# main_circuit.net
KiCad netlist of a schematic drawn in EAGLE
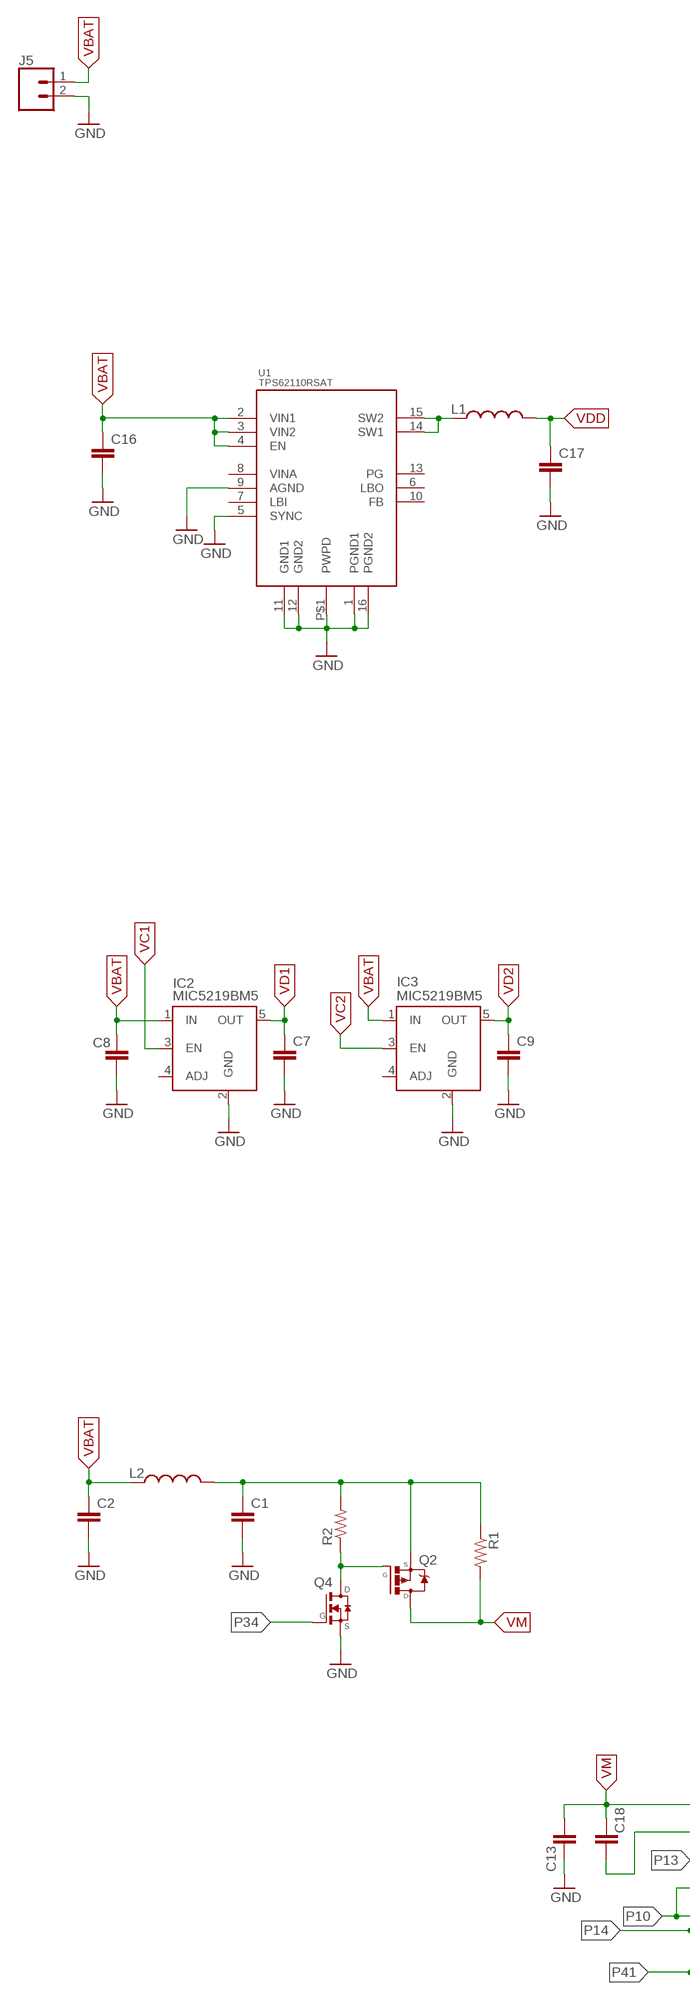
[diagram p0: schematic, sheet 1, part 1 of 2]
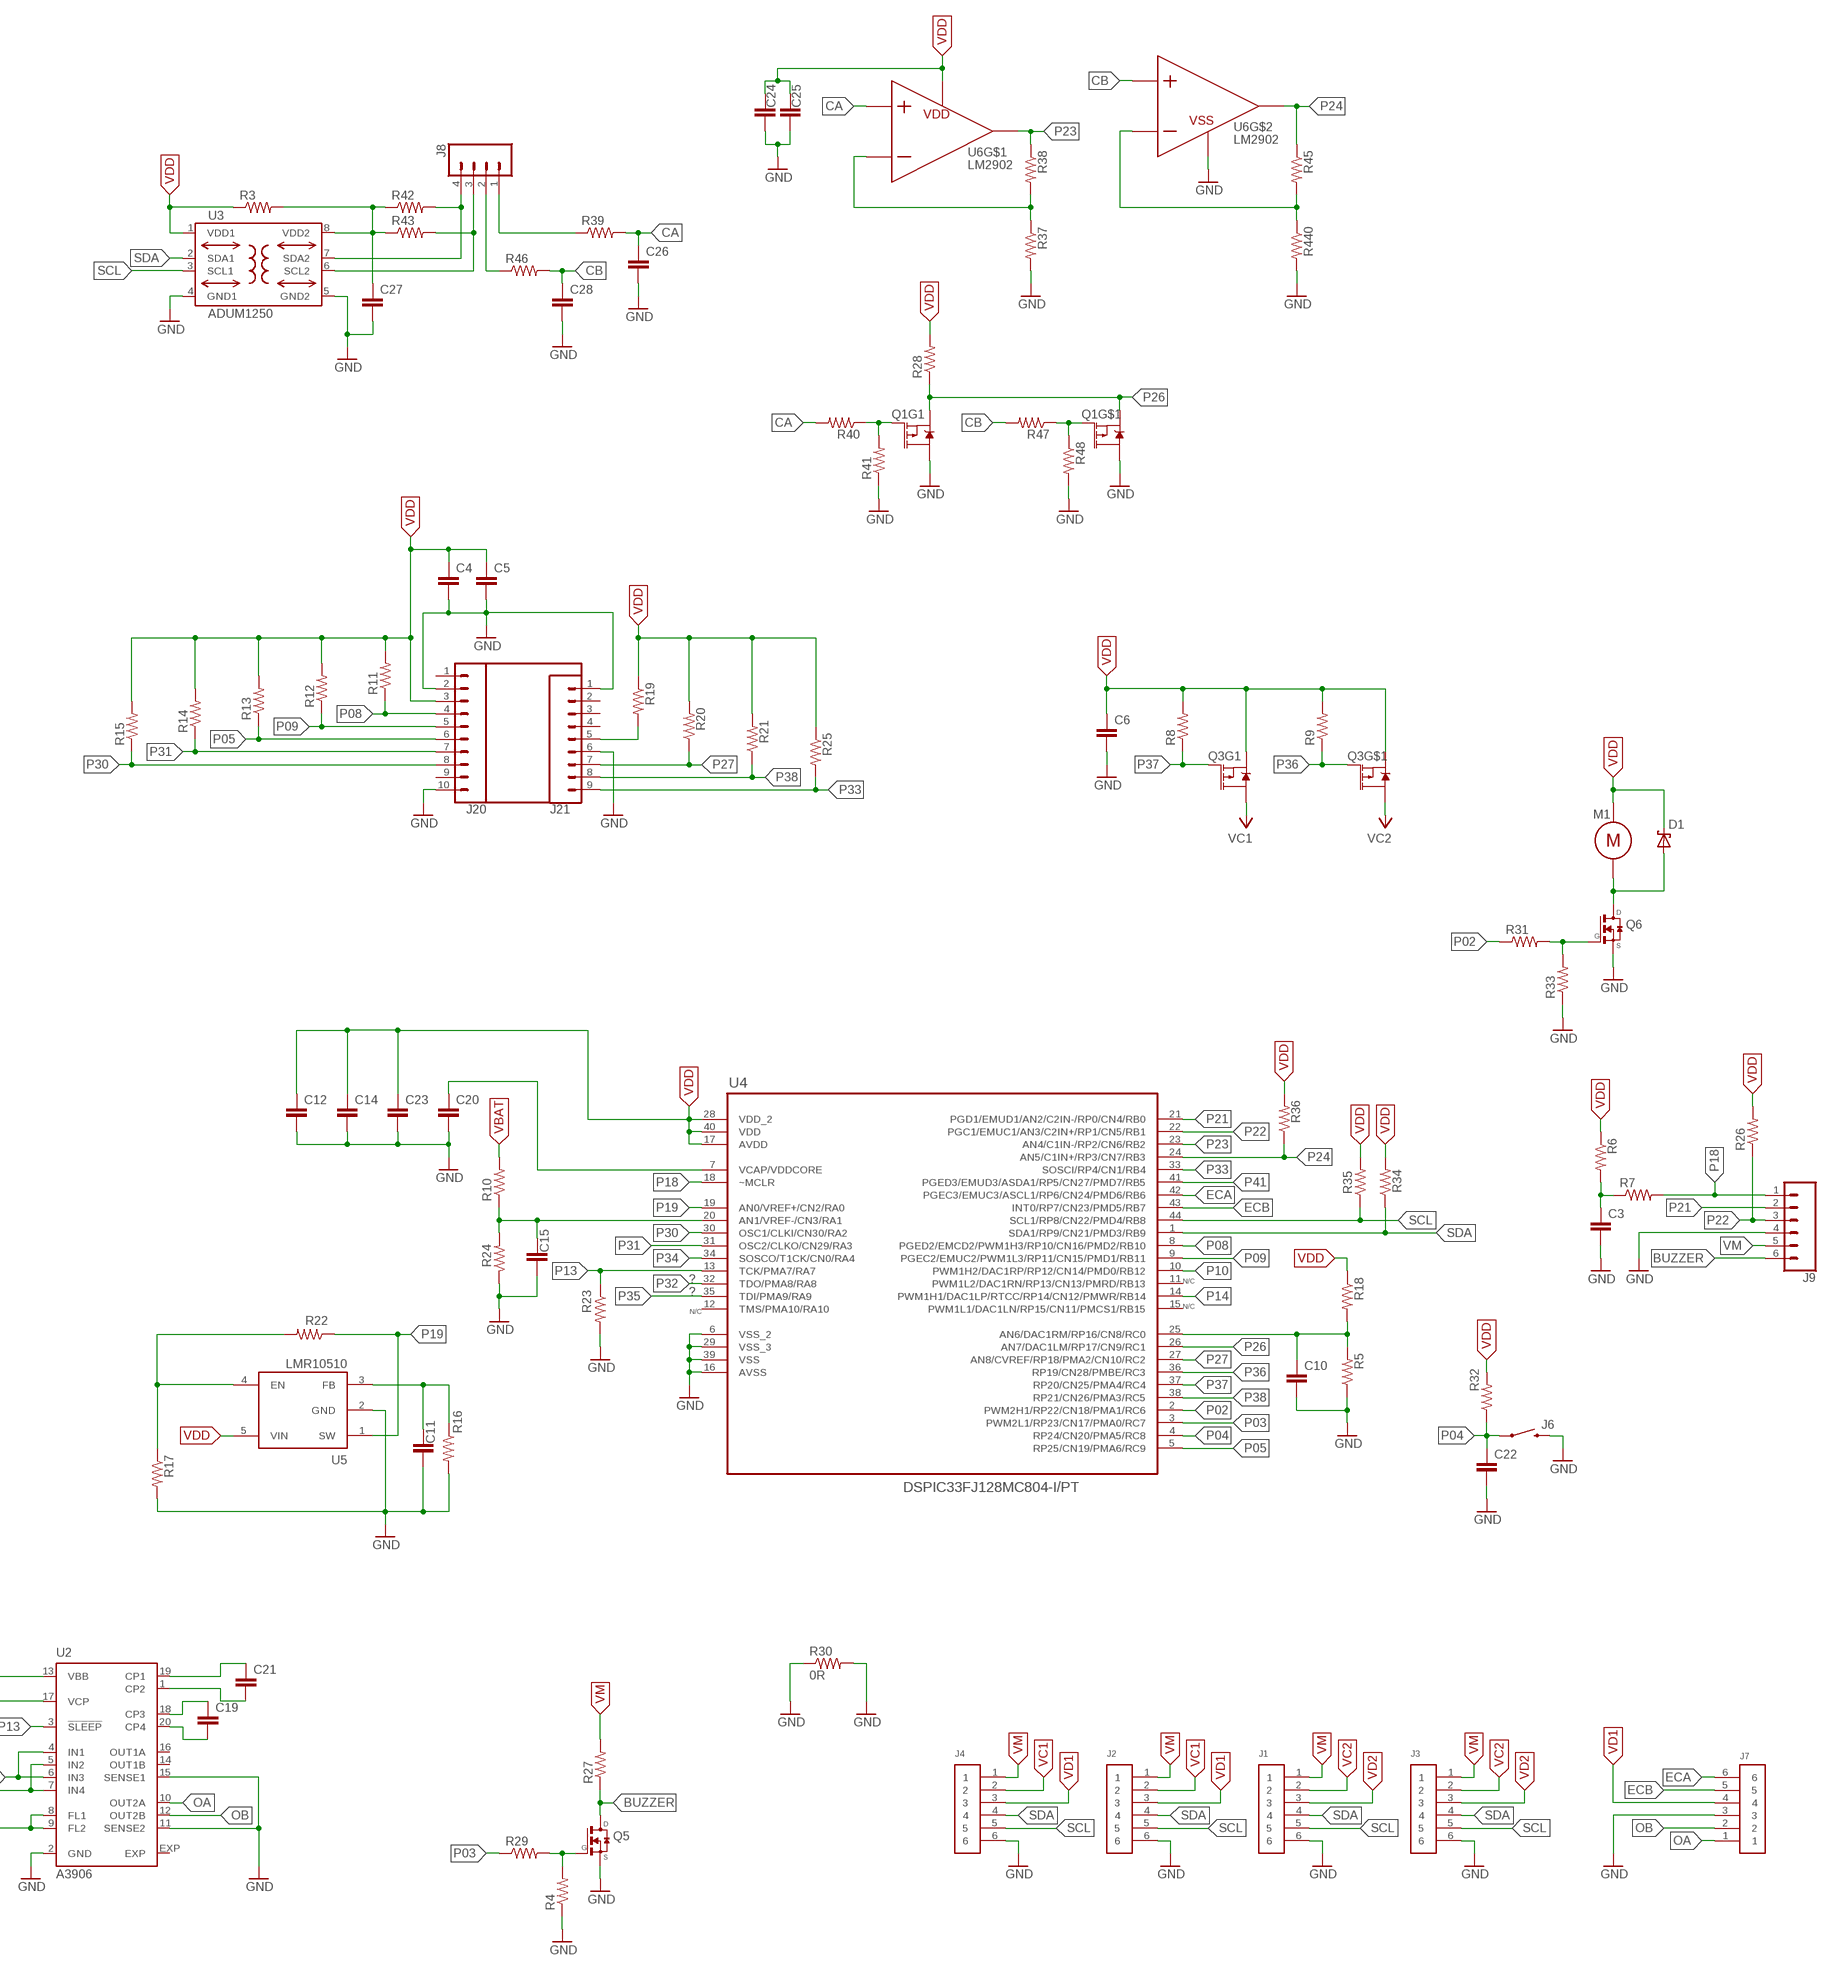
[diagram p1: schematic, sheet 1, part 2 of 2]

(export (version "E")
  (design (tool "Eeschema 10.0.6"))
  (components
    (comp (ref "C1")
      (value "C-EUC0805")
      (footprint "eagle-import:C0805")
      (libsource (lib "eagle-import") (part "C-EUC0805"))
    )
    (comp (ref "C2")
      (value "C-EUC0805")
      (footprint "eagle-import:C0805")
      (libsource (lib "eagle-import") (part "C-EUC0805"))
    )
    (comp (ref "C3")
      (value "CAPACITOR_0805_M")
      (footprint "eagle-import:RESC0805_M")
      (libsource (lib "eagle-import") (part "CAPACITOR_0805_M"))
    )
    (comp (ref "C4")
      (value "CAPACITOR_0805_M")
      (footprint "eagle-import:RESC0805_M")
      (libsource (lib "eagle-import") (part "CAPACITOR_0805_M"))
    )
    (comp (ref "C5")
      (value "CAPACITOR_0805_M")
      (footprint "eagle-import:RESC0805_M")
      (libsource (lib "eagle-import") (part "CAPACITOR_0805_M"))
    )
    (comp (ref "C6")
      (value "C-EUC0805")
      (footprint "eagle-import:C0805")
      (libsource (lib "eagle-import") (part "C-EUC0805"))
    )
    (comp (ref "C7")
      (value "CAPACITOR_0805_M")
      (footprint "eagle-import:RESC0805_M")
      (libsource (lib "eagle-import") (part "CAPACITOR_0805_M"))
    )
    (comp (ref "C8")
      (value "CAPACITOR_0805_M")
      (footprint "eagle-import:RESC0805_M")
      (libsource (lib "eagle-import") (part "CAPACITOR_0805_M"))
    )
    (comp (ref "C9")
      (value "CAPACITOR_0805_M")
      (footprint "eagle-import:RESC0805_M")
      (libsource (lib "eagle-import") (part "CAPACITOR_0805_M"))
    )
    (comp (ref "C10")
      (value "CAPACITOR_0805_M")
      (footprint "eagle-import:RESC0805_M")
      (libsource (lib "eagle-import") (part "CAPACITOR_0805_M"))
    )
    (comp (ref "C11")
      (value "CAPACITOR_0805_M")
      (footprint "eagle-import:RESC0805_M")
      (libsource (lib "eagle-import") (part "CAPACITOR_0805_M"))
    )
    (comp (ref "C12")
      (value "CAPACITOR_0805_M")
      (footprint "eagle-import:RESC0805_M")
      (libsource (lib "eagle-import") (part "CAPACITOR_0805_M"))
    )
    (comp (ref "C13")
      (value "CAPACITOR_0805_M")
      (footprint "eagle-import:RESC0805_M")
      (libsource (lib "eagle-import") (part "CAPACITOR_0805_M"))
    )
    (comp (ref "C14")
      (value "CAPACITOR_0805_M")
      (footprint "eagle-import:RESC0805_M")
      (libsource (lib "eagle-import") (part "CAPACITOR_0805_M"))
    )
    (comp (ref "C15")
      (value "CAPACITOR_0805_M")
      (footprint "eagle-import:RESC0805_M")
      (libsource (lib "eagle-import") (part "CAPACITOR_0805_M"))
    )
    (comp (ref "C16")
      (value "CAPACITOR_0805_M")
      (footprint "eagle-import:RESC0805_M")
      (libsource (lib "eagle-import") (part "CAPACITOR_0805_M"))
    )
    (comp (ref "C17")
      (value "CAPACITOR_0805_M")
      (footprint "eagle-import:RESC0805_M")
      (libsource (lib "eagle-import") (part "CAPACITOR_0805_M"))
    )
    (comp (ref "C18")
      (value "CAPACITOR_0805_M")
      (footprint "eagle-import:RESC0805_M")
      (libsource (lib "eagle-import") (part "CAPACITOR_0805_M"))
    )
    (comp (ref "C19")
      (value "CAPACITOR_0805_M")
      (footprint "eagle-import:RESC0805_M")
      (libsource (lib "eagle-import") (part "CAPACITOR_0805_M"))
    )
    (comp (ref "C20")
      (value "CAPACITOR_0805_M")
      (footprint "eagle-import:RESC0805_M")
      (libsource (lib "eagle-import") (part "CAPACITOR_0805_M"))
    )
    (comp (ref "C21")
      (value "CAPACITOR_0805_M")
      (footprint "eagle-import:RESC0805_M")
      (libsource (lib "eagle-import") (part "CAPACITOR_0805_M"))
    )
    (comp (ref "C22")
      (value "CAPACITOR_0805_M")
      (footprint "eagle-import:RESC0805_M")
      (libsource (lib "eagle-import") (part "CAPACITOR_0805_M"))
    )
    (comp (ref "C23")
      (value "CAPACITOR_0805_M")
      (footprint "eagle-import:RESC0805_M")
      (libsource (lib "eagle-import") (part "CAPACITOR_0805_M"))
    )
    (comp (ref "C24")
      (value "CAPACITOR_0805_M")
      (footprint "eagle-import:RESC0805_M")
      (libsource (lib "eagle-import") (part "CAPACITOR_0805_M"))
    )
    (comp (ref "C25")
      (value "CAPACITOR_0805_M")
      (footprint "eagle-import:RESC0805_M")
      (libsource (lib "eagle-import") (part "CAPACITOR_0805_M"))
    )
    (comp (ref "C26")
      (value "CAPACITOR_0805_M")
      (footprint "eagle-import:RESC0805_M")
      (libsource (lib "eagle-import") (part "CAPACITOR_0805_M"))
    )
    (comp (ref "C27")
      (value "CAPACITOR_0805_M")
      (footprint "eagle-import:RESC0805_M")
      (libsource (lib "eagle-import") (part "CAPACITOR_0805_M"))
    )
    (comp (ref "C28")
      (value "CAPACITOR_0805_M")
      (footprint "eagle-import:RESC0805_M")
      (libsource (lib "eagle-import") (part "CAPACITOR_0805_M"))
    )
    (comp (ref "D1")
      (value "BAS70W,115")
      (footprint "eagle-import:SOT323")
      (fields (field (name "MF") "Nexperia USA"))
      (libsource (lib "eagle-import") (part "BAS70W,115"))
    )
    (comp (ref "IC2")
      (value "MIC5219BM5")
      (footprint "eagle-import:SOT23-5")
      (fields (field (name "MF") "ALTERA CORPORATION") (field (name "MPN") "MIC5219BM5 TR"))
      (libsource (lib "eagle-import") (part "MIC5219BM5"))
    )
    (comp (ref "IC3")
      (value "MIC5219BM5")
      (footprint "eagle-import:SOT23-5")
      (fields (field (name "MF") "ALTERA CORPORATION") (field (name "MPN") "MIC5219BM5 TR"))
      (libsource (lib "eagle-import") (part "MIC5219BM5"))
    )
    (comp (ref "J1")
      (value "61300611121")
      (footprint "eagle-import:61300611121")
      (fields
        (field (name "DIGI_KEY_PART_NUMBER") "732-5319-ND")
        (field (name "MANUFACTURER") "Wurth Electronics Inc.")
        (field (name "CREATED_BY") "PCBLayout.com")
      )
      (libsource (lib "eagle-import") (part "61300611121"))
    )
    (comp (ref "J2")
      (value "61300611121")
      (footprint "eagle-import:61300611121")
      (fields
        (field (name "DIGI_KEY_PART_NUMBER") "732-5319-ND")
        (field (name "MANUFACTURER") "Wurth Electronics Inc.")
        (field (name "CREATED_BY") "PCBLayout.com")
      )
      (libsource (lib "eagle-import") (part "61300611121"))
    )
    (comp (ref "J3")
      (value "61300611121")
      (footprint "eagle-import:61300611121")
      (fields
        (field (name "DIGI_KEY_PART_NUMBER") "732-5319-ND")
        (field (name "MANUFACTURER") "Wurth Electronics Inc.")
        (field (name "CREATED_BY") "PCBLayout.com")
      )
      (libsource (lib "eagle-import") (part "61300611121"))
    )
    (comp (ref "J4")
      (value "61300611121")
      (footprint "eagle-import:61300611121")
      (fields
        (field (name "DIGI_KEY_PART_NUMBER") "732-5319-ND")
        (field (name "MANUFACTURER") "Wurth Electronics Inc.")
        (field (name "CREATED_BY") "PCBLayout.com")
      )
      (libsource (lib "eagle-import") (part "61300611121"))
    )
    (comp (ref "J5")
      (value "CONN_02-JST-2MM-SMT")
      (footprint "eagle-import:JST-2-SMD")
      (libsource (lib "eagle-import") (part "CONN_02-JST-2MM-SMT"))
    )
    (comp (ref "J6")
      (value "RS032G05A3SM-SPST-MOMENTARY-SWSMD-1101NE")
      (footprint "eagle-import:TACTILE-SWITCH-1101NE")
      (libsource (lib "eagle-import") (part "RS032G05A3SM-SPST-MOMENTARY-SWSMD-1101NE"))
    )
    (comp (ref "J7")
      (value "61300611121")
      (footprint "eagle-import:61300611121")
      (fields
        (field (name "DIGI_KEY_PART_NUMBER") "732-5319-ND")
        (field (name "MANUFACTURER") "Wurth Electronics Inc.")
        (field (name "CREATED_BY") "PCBLayout.com")
      )
      (libsource (lib "eagle-import") (part "61300611121"))
    )
    (comp (ref "J8")
      (value "CONN_04SMD2")
      (footprint "eagle-import:1X04_1MM_RA")
      (libsource (lib "eagle-import") (part "CONN_04SMD2"))
    )
    (comp (ref "J9")
      (value "CONN_06SMD-1MM")
      (footprint "eagle-import:1X06-1MM")
      (libsource (lib "eagle-import") (part "CONN_06SMD-1MM"))
    )
    (comp (ref "J20")
      (value "CONN_10\"")
      (footprint "eagle-import:1X10")
      (libsource (lib "eagle-import") (part "CONN_10{dblquote}"))
    )
    (comp (ref "J21")
      (value "CONN_09")
      (footprint "eagle-import:1X09")
      (libsource (lib "eagle-import") (part "CONN_09"))
    )
    (comp (ref "L1")
      (value "INDUCTOR")
      (footprint "eagle-import:L0603")
      (libsource (lib "eagle-import") (part "INDUCTOR"))
    )
    (comp (ref "L2")
      (value "INDUCTOR")
      (footprint "eagle-import:L0603")
      (libsource (lib "eagle-import") (part "INDUCTOR"))
    )
    (comp (ref "M1")
      (value "308-100")
      (footprint "eagle-import:308-100")
      (libsource (lib "eagle-import") (part "308-100"))
    )
    (comp (ref "Q1")
      (value "2A/20V/150mΩ")
      (footprint "eagle-import:SOT26")
      (libsource (lib "eagle-import") (part "MOSFET_PCH_DUAL-DMP2240UDM"))
    )
    (comp (ref "Q2")
      (value "FDS6675")
      (footprint "eagle-import:SO08-E3")
      (fields (field (name "MF") "ON Semiconductor"))
      (libsource (lib "eagle-import") (part "FDS6675"))
    )
    (comp (ref "Q3")
      (value "2A/20V/150mΩ")
      (footprint "eagle-import:SOT26")
      (libsource (lib "eagle-import") (part "MOSFET_PCH_DUAL-DMP2240UDM"))
    )
    (comp (ref "Q4")
      (value "FDV303N")
      (footprint "eagle-import:SOT23")
      (fields (field (name "MF") "Fairchild Semiconductor") (field (name "MP") "FDV303N."))
      (libsource (lib "eagle-import") (part "FDV303N"))
    )
    (comp (ref "Q5")
      (value "FDV303N")
      (footprint "eagle-import:SOT23")
      (fields (field (name "MF") "Fairchild Semiconductor") (field (name "MP") "FDV303N."))
      (libsource (lib "eagle-import") (part "FDV303N"))
    )
    (comp (ref "Q6")
      (value "FDV303N")
      (footprint "eagle-import:SOT23")
      (fields (field (name "MF") "Fairchild Semiconductor") (field (name "MP") "FDV303N."))
      (libsource (lib "eagle-import") (part "FDV303N"))
    )
    (comp (ref "R1")
      (value "R-US_M0805")
      (footprint "eagle-import:M0805")
      (libsource (lib "eagle-import") (part "R-US_M0805"))
    )
    (comp (ref "R2")
      (value "R-US_M0805")
      (footprint "eagle-import:M0805")
      (libsource (lib "eagle-import") (part "R-US_M0805"))
    )
    (comp (ref "R3")
      (value "R-US_M0805")
      (footprint "eagle-import:M0805")
      (libsource (lib "eagle-import") (part "R-US_M0805"))
    )
    (comp (ref "R4")
      (value "R-US_M0805")
      (footprint "eagle-import:M0805")
      (libsource (lib "eagle-import") (part "R-US_M0805"))
    )
    (comp (ref "R5")
      (value "R-US_M0805")
      (footprint "eagle-import:M0805")
      (libsource (lib "eagle-import") (part "R-US_M0805"))
    )
    (comp (ref "R6")
      (value "R-US_M0805")
      (footprint "eagle-import:M0805")
      (libsource (lib "eagle-import") (part "R-US_M0805"))
    )
    (comp (ref "R7")
      (value "R-US_M0805")
      (footprint "eagle-import:M0805")
      (libsource (lib "eagle-import") (part "R-US_M0805"))
    )
    (comp (ref "R8")
      (value "R-US_M0805")
      (footprint "eagle-import:M0805")
      (libsource (lib "eagle-import") (part "R-US_M0805"))
    )
    (comp (ref "R9")
      (value "R-US_M0805")
      (footprint "eagle-import:M0805")
      (libsource (lib "eagle-import") (part "R-US_M0805"))
    )
    (comp (ref "R10")
      (value "R-US_M0805")
      (footprint "eagle-import:M0805")
      (libsource (lib "eagle-import") (part "R-US_M0805"))
    )
    (comp (ref "R11")
      (value "R-US_M0805")
      (footprint "eagle-import:M0805")
      (libsource (lib "eagle-import") (part "R-US_M0805"))
    )
    (comp (ref "R12")
      (value "R-US_M0805")
      (footprint "eagle-import:M0805")
      (libsource (lib "eagle-import") (part "R-US_M0805"))
    )
    (comp (ref "R13")
      (value "R-US_M0805")
      (footprint "eagle-import:M0805")
      (libsource (lib "eagle-import") (part "R-US_M0805"))
    )
    (comp (ref "R14")
      (value "R-US_M0805")
      (footprint "eagle-import:M0805")
      (libsource (lib "eagle-import") (part "R-US_M0805"))
    )
    (comp (ref "R15")
      (value "R-US_M0805")
      (footprint "eagle-import:M0805")
      (libsource (lib "eagle-import") (part "R-US_M0805"))
    )
    (comp (ref "R16")
      (value "R-US_R0805")
      (footprint "eagle-import:R0805")
      (libsource (lib "eagle-import") (part "R-US_R0805"))
    )
    (comp (ref "R17")
      (value "R-US_R0805")
      (footprint "eagle-import:R0805")
      (libsource (lib "eagle-import") (part "R-US_R0805"))
    )
    (comp (ref "R18")
      (value "R-US_M0805")
      (footprint "eagle-import:M0805")
      (libsource (lib "eagle-import") (part "R-US_M0805"))
    )
    (comp (ref "R19")
      (value "R-US_M0805")
      (footprint "eagle-import:M0805")
      (libsource (lib "eagle-import") (part "R-US_M0805"))
    )
    (comp (ref "R20")
      (value "R-US_M0805")
      (footprint "eagle-import:M0805")
      (libsource (lib "eagle-import") (part "R-US_M0805"))
    )
    (comp (ref "R21")
      (value "R-US_M0805")
      (footprint "eagle-import:M0805")
      (libsource (lib "eagle-import") (part "R-US_M0805"))
    )
    (comp (ref "R22")
      (value "R-US_R0805")
      (footprint "eagle-import:R0805")
      (libsource (lib "eagle-import") (part "R-US_R0805"))
    )
    (comp (ref "R23")
      (value "R-US_M0805")
      (footprint "eagle-import:M0805")
      (libsource (lib "eagle-import") (part "R-US_M0805"))
    )
    (comp (ref "R24")
      (value "R-US_M0805")
      (footprint "eagle-import:M0805")
      (libsource (lib "eagle-import") (part "R-US_M0805"))
    )
    (comp (ref "R25")
      (value "R-US_M0805")
      (footprint "eagle-import:M0805")
      (libsource (lib "eagle-import") (part "R-US_M0805"))
    )
    (comp (ref "R26")
      (value "R-US_M0805")
      (footprint "eagle-import:M0805")
      (libsource (lib "eagle-import") (part "R-US_M0805"))
    )
    (comp (ref "R27")
      (value "R-US_M0805")
      (footprint "eagle-import:M0805")
      (libsource (lib "eagle-import") (part "R-US_M0805"))
    )
    (comp (ref "R28")
      (value "R-US_M0805")
      (footprint "eagle-import:M0805")
      (libsource (lib "eagle-import") (part "R-US_M0805"))
    )
    (comp (ref "R29")
      (value "R-US_M0805")
      (footprint "eagle-import:M0805")
      (libsource (lib "eagle-import") (part "R-US_M0805"))
    )
    (comp (ref "R30")
      (value "0R")
      (footprint "eagle-import:M0805")
      (libsource (lib "eagle-import") (part "R-US_M0805"))
    )
    (comp (ref "R31")
      (value "R-US_M0805")
      (footprint "eagle-import:M0805")
      (libsource (lib "eagle-import") (part "R-US_M0805"))
    )
    (comp (ref "R32")
      (value "R-US_M0805")
      (footprint "eagle-import:M0805")
      (libsource (lib "eagle-import") (part "R-US_M0805"))
    )
    (comp (ref "R33")
      (value "R-US_M0805")
      (footprint "eagle-import:M0805")
      (libsource (lib "eagle-import") (part "R-US_M0805"))
    )
    (comp (ref "R34")
      (value "R-US_M0805")
      (footprint "eagle-import:M0805")
      (libsource (lib "eagle-import") (part "R-US_M0805"))
    )
    (comp (ref "R35")
      (value "R-US_M0805")
      (footprint "eagle-import:M0805")
      (libsource (lib "eagle-import") (part "R-US_M0805"))
    )
    (comp (ref "R36")
      (value "R-US_M0805")
      (footprint "eagle-import:M0805")
      (libsource (lib "eagle-import") (part "R-US_M0805"))
    )
    (comp (ref "R37")
      (value "R-US_M0805")
      (footprint "eagle-import:M0805")
      (libsource (lib "eagle-import") (part "R-US_M0805"))
    )
    (comp (ref "R38")
      (value "R-US_M0805")
      (footprint "eagle-import:M0805")
      (libsource (lib "eagle-import") (part "R-US_M0805"))
    )
    (comp (ref "R39")
      (value "R-US_M0805")
      (footprint "eagle-import:M0805")
      (libsource (lib "eagle-import") (part "R-US_M0805"))
    )
    (comp (ref "R40")
      (value "R-US_M0805")
      (footprint "eagle-import:M0805")
      (libsource (lib "eagle-import") (part "R-US_M0805"))
    )
    (comp (ref "R41")
      (value "R-US_M0805")
      (footprint "eagle-import:M0805")
      (libsource (lib "eagle-import") (part "R-US_M0805"))
    )
    (comp (ref "R42")
      (value "R-US_M0805")
      (footprint "eagle-import:M0805")
      (libsource (lib "eagle-import") (part "R-US_M0805"))
    )
    (comp (ref "R43")
      (value "R-US_M0805")
      (footprint "eagle-import:M0805")
      (libsource (lib "eagle-import") (part "R-US_M0805"))
    )
    (comp (ref "R45")
      (value "R-US_M0805")
      (footprint "eagle-import:M0805")
      (libsource (lib "eagle-import") (part "R-US_M0805"))
    )
    (comp (ref "R46")
      (value "R-US_M0805")
      (footprint "eagle-import:M0805")
      (libsource (lib "eagle-import") (part "R-US_M0805"))
    )
    (comp (ref "R47")
      (value "R-US_M0805")
      (footprint "eagle-import:M0805")
      (libsource (lib "eagle-import") (part "R-US_M0805"))
    )
    (comp (ref "R48")
      (value "R-US_M0805")
      (footprint "eagle-import:M0805")
      (libsource (lib "eagle-import") (part "R-US_M0805"))
    )
    (comp (ref "R440")
      (value "R-US_M0805")
      (footprint "eagle-import:M0805")
      (libsource (lib "eagle-import") (part "R-US_M0805"))
    )
    (comp (ref "U1")
      (value "TPS62110RSAT")
      (footprint "eagle-import:QFN16")
      (libsource (lib "eagle-import") (part "TPS62110RSAT"))
    )
    (comp (ref "U2")
      (value "A3906")
      (footprint "eagle-import:QFN20")
      (libsource (lib "eagle-import") (part "A3906"))
    )
    (comp (ref "U3")
      (value "ADUM1250")
      (footprint "eagle-import:SO8-COOL")
      (fields (field (name "MF") "Analog Devices"))
      (libsource (lib "eagle-import") (part "ADUM1250"))
    )
    (comp (ref "U4")
      (value "DSPIC33FJ128MC804-I/PT")
      (footprint "eagle-import:QFP80P1200X1200X120-44N")
      (fields (field (name "MF") "Microchip"))
      (libsource (lib "eagle-import") (part "DSPIC33FJ128MC804-I/PT"))
    )
    (comp (ref "U5")
      (value "LMR10510")
      (footprint "eagle-import:SOT-23-5")
      (fields
        (field (name "DIGIKEY_PART_NUMBER") "LMR10510YMFE/NOPBTR-ND")
        (field (name "MANUFACTURER") "Texas Instruments")
        (field (name "MPN") "LMR10510YMFE/NOPB")
        (field (name "CREATED_BY") "PCBLayout.com")
      )
      (libsource (lib "eagle-import") (part "LMR10510YMFE/NOPB"))
    )
    (comp (ref "U6")
      (value "LM2902")
      (footprint "eagle-import:TSSOP8")
      (libsource (lib "eagle-import") (part "LM2902"))
    )
  )
  (nets
    (net (code "1") (name "BUZZER") (class "Default")
      (node (ref "J9") (pin "6") (pinfunction "6_6") (pintype "passive"))
      (node (ref "Q5") (pin "3") (pinfunction "D_3") (pintype "passive"))
      (node (ref "R27") (pin "1") (pinfunction "1_1") (pintype "passive"))
    )
    (net (code "2") (name "CA") (class "Default")
      (node (ref "C26") (pin "1") (pinfunction "1_1") (pintype "passive"))
      (node (ref "R39") (pin "2") (pinfunction "2_2") (pintype "passive"))
      (node (ref "R40") (pin "2") (pinfunction "2_2") (pintype "passive"))
      (node (ref "U6") (pin "3") (pinfunction "P_3") (pintype "bidirectional"))
    )
    (net (code "3") (name "CB") (class "Default")
      (node (ref "C28") (pin "1") (pinfunction "1_1") (pintype "passive"))
      (node (ref "R46") (pin "2") (pinfunction "2_2") (pintype "passive"))
      (node (ref "R47") (pin "2") (pinfunction "2_2") (pintype "passive"))
      (node (ref "U6") (pin "5") (pinfunction "P1_5") (pintype "bidirectional"))
    )
    (net (code "4") (name "ECA") (class "Default")
      (node (ref "J7") (pin "6") (pinfunction "6_6") (pintype "passive"))
      (node (ref "U4") (pin "42") (pinfunction "PGEC3/EMUC3/ASCL1/RP6/CN24/PMD6/RB6_42") (pintype "bidirectional"))
    )
    (net (code "5") (name "ECB") (class "Default")
      (node (ref "J7") (pin "5") (pinfunction "5_5") (pintype "passive"))
      (node (ref "U4") (pin "43") (pinfunction "INT0/RP7/CN23/PMD5/RB7_43") (pintype "bidirectional"))
    )
    (net (code "6") (name "GND") (class "Default")
      (node (ref "C1") (pin "2") (pinfunction "2_2") (pintype "passive"))
      (node (ref "C10") (pin "2") (pinfunction "2_2") (pintype "passive"))
      (node (ref "C11") (pin "2") (pinfunction "2_2") (pintype "passive"))
      (node (ref "C12") (pin "2") (pinfunction "2_2") (pintype "passive"))
      (node (ref "C13") (pin "1") (pinfunction "1_1") (pintype "passive"))
      (node (ref "C14") (pin "2") (pinfunction "2_2") (pintype "passive"))
      (node (ref "C15") (pin "2") (pinfunction "2_2") (pintype "passive"))
      (node (ref "C16") (pin "2") (pinfunction "2_2") (pintype "passive"))
      (node (ref "C17") (pin "2") (pinfunction "2_2") (pintype "passive"))
      (node (ref "C2") (pin "2") (pinfunction "2_2") (pintype "passive"))
      (node (ref "C20") (pin "2") (pinfunction "2_2") (pintype "passive"))
      (node (ref "C22") (pin "2") (pinfunction "2_2") (pintype "passive"))
      (node (ref "C23") (pin "2") (pinfunction "2_2") (pintype "passive"))
      (node (ref "C24") (pin "2") (pinfunction "2_2") (pintype "passive"))
      (node (ref "C25") (pin "2") (pinfunction "2_2") (pintype "passive"))
      (node (ref "C26") (pin "2") (pinfunction "2_2") (pintype "passive"))
      (node (ref "C27") (pin "2") (pinfunction "2_2") (pintype "passive"))
      (node (ref "C28") (pin "2") (pinfunction "2_2") (pintype "passive"))
      (node (ref "C3") (pin "2") (pinfunction "2_2") (pintype "passive"))
      (node (ref "C4") (pin "2") (pinfunction "2_2") (pintype "passive"))
      (node (ref "C5") (pin "2") (pinfunction "2_2") (pintype "passive"))
      (node (ref "C6") (pin "2") (pinfunction "2_2") (pintype "passive"))
      (node (ref "C7") (pin "2") (pinfunction "2_2") (pintype "passive"))
      (node (ref "C8") (pin "2") (pinfunction "2_2") (pintype "passive"))
      (node (ref "C9") (pin "2") (pinfunction "2_2") (pintype "passive"))
      (node (ref "IC2") (pin "2") (pinfunction "GND_2") (pintype "power_in"))
      (node (ref "IC3") (pin "2") (pinfunction "GND_2") (pintype "power_in"))
      (node (ref "J1") (pin "6") (pinfunction "6_6") (pintype "passive"))
      (node (ref "J2") (pin "6") (pinfunction "6_6") (pintype "passive"))
      (node (ref "J20") (pin "10") (pinfunction "10_10") (pintype "passive"))
      (node (ref "J20") (pin "2") (pinfunction "2_2") (pintype "passive"))
      (node (ref "J21") (pin "1") (pinfunction "1_1") (pintype "passive"))
      (node (ref "J21") (pin "6") (pinfunction "6_6") (pintype "passive"))
      (node (ref "J3") (pin "6") (pinfunction "6_6") (pintype "passive"))
      (node (ref "J4") (pin "6") (pinfunction "6_6") (pintype "passive"))
      (node (ref "J5") (pin "2") (pinfunction "1_2") (pintype "passive"))
      (node (ref "J6") (pin "2") (pinfunction "2_2") (pintype "passive"))
      (node (ref "J7") (pin "3") (pinfunction "3_3") (pintype "passive"))
      (node (ref "J9") (pin "4") (pinfunction "4_4") (pintype "passive"))
      (node (ref "Q1") (pin "D1") (pinfunction "D_D1") (pintype "bidirectional"))
      (node (ref "Q1") (pin "D2") (pinfunction "D_D2") (pintype "bidirectional"))
      (node (ref "Q4") (pin "2") (pinfunction "S_2") (pintype "passive"))
      (node (ref "Q5") (pin "2") (pinfunction "S_2") (pintype "passive"))
      (node (ref "Q6") (pin "2") (pinfunction "S_2") (pintype "passive"))
      (node (ref "R16") (pin "2") (pinfunction "2_2") (pintype "passive"))
      (node (ref "R17") (pin "2") (pinfunction "2_2") (pintype "passive"))
      (node (ref "R23") (pin "2") (pinfunction "2_2") (pintype "passive"))
      (node (ref "R24") (pin "1") (pinfunction "1_1") (pintype "passive"))
      (node (ref "R30") (pin "1") (pinfunction "1_1") (pintype "passive"))
      (node (ref "R30") (pin "2") (pinfunction "2_2") (pintype "passive"))
      (node (ref "R33") (pin "1") (pinfunction "1_1") (pintype "passive"))
      (node (ref "R37") (pin "2") (pinfunction "2_2") (pintype "passive"))
      (node (ref "R4") (pin "1") (pinfunction "1_1") (pintype "passive"))
      (node (ref "R41") (pin "1") (pinfunction "1_1") (pintype "passive"))
      (node (ref "R440") (pin "2") (pinfunction "2_2") (pintype "passive"))
      (node (ref "R48") (pin "2") (pinfunction "2_2") (pintype "passive"))
      (node (ref "R5") (pin "1") (pinfunction "1_1") (pintype "passive"))
      (node (ref "U1") (pin "1") (pinfunction "PGND1_1") (pintype "input"))
      (node (ref "U1") (pin "11") (pinfunction "GND1_11") (pintype "input"))
      (node (ref "U1") (pin "12") (pinfunction "GND2_12") (pintype "input"))
      (node (ref "U1") (pin "16") (pinfunction "PGND2_16") (pintype "bidirectional"))
      (node (ref "U1") (pin "5") (pinfunction "SYNC_5") (pintype "input"))
      (node (ref "U1") (pin "9") (pinfunction "AGND_9") (pintype "input"))
      (node (ref "U1") (pin "P$1") (pinfunction "PWPD_P$1") (pintype "input"))
      (node (ref "U2") (pin "11") (pinfunction "SENSE2_11") (pintype "input"))
      (node (ref "U2") (pin "15") (pinfunction "SENSE1_15") (pintype "input"))
      (node (ref "U2") (pin "2") (pinfunction "GND_2") (pintype "power_in"))
      (node (ref "U3") (pin "4") (pinfunction "GND1_4") (pintype "power_in"))
      (node (ref "U3") (pin "5") (pinfunction "GND2_5") (pintype "power_in"))
      (node (ref "U4") (pin "16") (pinfunction "AVSS_16") (pintype "passive"))
      (node (ref "U4") (pin "29") (pinfunction "VSS_3_29") (pintype "passive"))
      (node (ref "U4") (pin "39") (pinfunction "VSS_39") (pintype "passive"))
      (node (ref "U4") (pin "6") (pinfunction "VSS_2_6") (pintype "passive"))
      (node (ref "U5") (pin "2") (pinfunction "GND_2") (pintype "power_in"))
      (node (ref "U6") (pin "4") (pinfunction "VSS_4") (pintype "power_in"))
    )
    (net (code "7") (name "Net-(C3-Pad1)") (class "Default")
      (node (ref "C3") (pin "1") (pinfunction "1_1") (pintype "passive"))
      (node (ref "R6") (pin "2") (pinfunction "2_2") (pintype "passive"))
      (node (ref "R7") (pin "1") (pinfunction "1_1") (pintype "passive"))
    )
    (net (code "8") (name "Net-(D1-A)") (class "Default")
      (node (ref "D1") (pin "1") (pinfunction "A_1") (pintype "passive"))
      (node (ref "M1") (pin "NEG") (pinfunction "NEG_NEG") (pintype "bidirectional"))
      (node (ref "Q6") (pin "3") (pinfunction "D_3") (pintype "passive"))
    )
    (net (code "9") (name "Net-(J8-Pad1)") (class "Default")
      (node (ref "J8") (pin "1") (pinfunction "1_1") (pintype "passive"))
      (node (ref "R39") (pin "1") (pinfunction "1_1") (pintype "passive"))
    )
    (net (code "10") (name "Net-(J8-Pad2)") (class "Default")
      (node (ref "J8") (pin "2") (pinfunction "2_2") (pintype "passive"))
      (node (ref "R46") (pin "1") (pinfunction "1_1") (pintype "passive"))
    )
    (net (code "11") (name "Net-(J21-Pad5)") (class "Default")
      (node (ref "J21") (pin "5") (pinfunction "5_5") (pintype "passive"))
      (node (ref "R19") (pin "2") (pinfunction "2_2") (pintype "passive"))
    )
    (net (code "12") (name "Net-(Q1A-G)") (class "Default")
      (node (ref "Q1") (pin "G2") (pinfunction "G_G2") (pintype "bidirectional"))
      (node (ref "R47") (pin "1") (pinfunction "1_1") (pintype "passive"))
      (node (ref "R48") (pin "1") (pinfunction "1_1") (pintype "passive"))
    )
    (net (code "13") (name "Net-(Q1B-G)") (class "Default")
      (node (ref "Q1") (pin "G1") (pinfunction "G_G1") (pintype "bidirectional"))
      (node (ref "R40") (pin "1") (pinfunction "1_1") (pintype "passive"))
      (node (ref "R41") (pin "2") (pinfunction "2_2") (pintype "passive"))
    )
    (net (code "14") (name "Net-(Q2-G)") (class "Default")
      (node (ref "Q2") (pin "4") (pinfunction "G_4") (pintype "passive"))
      (node (ref "Q4") (pin "3") (pinfunction "D_3") (pintype "passive"))
      (node (ref "R2") (pin "1") (pinfunction "1_1") (pintype "passive"))
    )
    (net (code "15") (name "Net-(Q2-S)") (class "Default")
      (node (ref "C1") (pin "1") (pinfunction "1_1") (pintype "passive"))
      (node (ref "L2") (pin "2") (pinfunction "2_2") (pintype "passive"))
      (node (ref "Q2") (pin "1-3") (pinfunction "S_1-3") (pintype "passive"))
      (node (ref "R1") (pin "1") (pinfunction "1_1") (pintype "passive"))
      (node (ref "R2") (pin "2") (pinfunction "2_2") (pintype "passive"))
    )
    (net (code "16") (name "Net-(Q5-G)") (class "Default")
      (node (ref "Q5") (pin "1") (pinfunction "G_1") (pintype "passive"))
      (node (ref "R29") (pin "2") (pinfunction "2_2") (pintype "passive"))
      (node (ref "R4") (pin "2") (pinfunction "2_2") (pintype "passive"))
    )
    (net (code "17") (name "Net-(Q6-G)") (class "Default")
      (node (ref "Q6") (pin "1") (pinfunction "G_1") (pintype "passive"))
      (node (ref "R31") (pin "2") (pinfunction "2_2") (pintype "passive"))
      (node (ref "R33") (pin "2") (pinfunction "2_2") (pintype "passive"))
    )
    (net (code "18") (name "Net-(U1-SW1)") (class "Default")
      (node (ref "L1") (pin "1") (pinfunction "1_1") (pintype "passive"))
      (node (ref "U1") (pin "14") (pinfunction "SW1_14") (pintype "output"))
      (node (ref "U1") (pin "15") (pinfunction "SW2_15") (pintype "output"))
    )
    (net (code "19") (name "Net-(U2-CP1)") (class "Default")
      (node (ref "C21") (pin "1") (pinfunction "1_1") (pintype "passive"))
      (node (ref "U2") (pin "19") (pinfunction "CP1_19") (pintype "passive"))
    )
    (net (code "20") (name "Net-(U2-CP2)") (class "Default")
      (node (ref "C21") (pin "2") (pinfunction "2_2") (pintype "passive"))
      (node (ref "U2") (pin "1") (pinfunction "CP2_1") (pintype "passive"))
    )
    (net (code "21") (name "Net-(U2-CP3)") (class "Default")
      (node (ref "C19") (pin "1") (pinfunction "1_1") (pintype "passive"))
      (node (ref "U2") (pin "18") (pinfunction "CP3_18") (pintype "passive"))
    )
    (net (code "22") (name "Net-(U2-CP4)") (class "Default")
      (node (ref "C19") (pin "2") (pinfunction "2_2") (pintype "passive"))
      (node (ref "U2") (pin "20") (pinfunction "CP4_20") (pintype "passive"))
    )
    (net (code "23") (name "Net-(U2-VCP)") (class "Default")
      (node (ref "C18") (pin "2") (pinfunction "2_2") (pintype "passive"))
      (node (ref "U2") (pin "17") (pinfunction "VCP_17") (pintype "passive"))
    )
    (net (code "24") (name "Net-(U3-SCL2)") (class "Default")
      (node (ref "J8") (pin "3") (pinfunction "3_3") (pintype "passive"))
      (node (ref "R43") (pin "2") (pinfunction "2_2") (pintype "passive"))
      (node (ref "U3") (pin "6") (pinfunction "SCL2_6") (pintype "bidirectional"))
    )
    (net (code "25") (name "Net-(U3-SDA2)") (class "Default")
      (node (ref "J8") (pin "4") (pinfunction "4_4") (pintype "passive"))
      (node (ref "R42") (pin "2") (pinfunction "2_2") (pintype "passive"))
      (node (ref "U3") (pin "7") (pinfunction "SDA2_7") (pintype "bidirectional"))
    )
    (net (code "26") (name "Net-(U3-VDD2)") (class "Default")
      (node (ref "C27") (pin "1") (pinfunction "1_1") (pintype "passive"))
      (node (ref "R3") (pin "2") (pinfunction "2_2") (pintype "passive"))
      (node (ref "R42") (pin "1") (pinfunction "1_1") (pintype "passive"))
      (node (ref "R43") (pin "1") (pinfunction "1_1") (pintype "passive"))
      (node (ref "U3") (pin "8") (pinfunction "VDD2_8") (pintype "power_in"))
    )
    (net (code "27") (name "Net-(U4-AN1{slash}VREF-{slash}CN3{slash}RA1)") (class "Default")
      (node (ref "C15") (pin "1") (pinfunction "1_1") (pintype "passive"))
      (node (ref "R10") (pin "1") (pinfunction "1_1") (pintype "passive"))
      (node (ref "R24") (pin "2") (pinfunction "2_2") (pintype "passive"))
      (node (ref "U4") (pin "20") (pinfunction "AN1/VREF-/CN3/RA1_20") (pintype "bidirectional"))
    )
    (net (code "28") (name "Net-(U4-AN6{slash}DAC1RM{slash}RP16{slash}CN8{slash}RC0)") (class "Default")
      (node (ref "C10") (pin "1") (pinfunction "1_1") (pintype "passive"))
      (node (ref "R18") (pin "2") (pinfunction "2_2") (pintype "passive"))
      (node (ref "R5") (pin "2") (pinfunction "2_2") (pintype "passive"))
      (node (ref "U4") (pin "25") (pinfunction "AN6/DAC1RM/RP16/CN8/RC0_25") (pintype "bidirectional"))
    )
    (net (code "29") (name "Net-(U4-VCAP{slash}VDDCORE)") (class "Default")
      (node (ref "C20") (pin "1") (pinfunction "1_1") (pintype "passive"))
      (node (ref "U4") (pin "7") (pinfunction "VCAP/VDDCORE_7") (pintype "power_in"))
    )
    (net (code "30") (name "Net-(U5-EN)") (class "Default")
      (node (ref "R17") (pin "1") (pinfunction "1_1") (pintype "passive"))
      (node (ref "R22") (pin "2") (pinfunction "2_2") (pintype "passive"))
      (node (ref "U5") (pin "4") (pinfunction "EN_4") (pintype "input"))
    )
    (net (code "31") (name "Net-(U5-FB)") (class "Default")
      (node (ref "C11") (pin "1") (pinfunction "1_1") (pintype "passive"))
      (node (ref "R16") (pin "1") (pinfunction "1_1") (pintype "passive"))
      (node (ref "U5") (pin "3") (pinfunction "FB_3") (pintype "output"))
    )
    (net (code "32") (name "Net-(U6A-N)") (class "Default")
      (node (ref "R37") (pin "1") (pinfunction "1_1") (pintype "passive"))
      (node (ref "R38") (pin "2") (pinfunction "2_2") (pintype "passive"))
      (node (ref "U6") (pin "2") (pinfunction "N_2") (pintype "bidirectional"))
    )
    (net (code "33") (name "Net-(U6B-N1)") (class "Default")
      (node (ref "R440") (pin "1") (pinfunction "1_1") (pintype "passive"))
      (node (ref "R45") (pin "2") (pinfunction "2_2") (pintype "passive"))
      (node (ref "U6") (pin "6") (pinfunction "N1_6") (pintype "bidirectional"))
    )
    (net (code "34") (name "OA") (class "Default")
      (node (ref "J7") (pin "1") (pinfunction "1_1") (pintype "passive"))
      (node (ref "U2") (pin "10") (pinfunction "OUT2A_10") (pintype "output"))
    )
    (net (code "35") (name "OB") (class "Default")
      (node (ref "J7") (pin "2") (pinfunction "2_2") (pintype "passive"))
      (node (ref "U2") (pin "12") (pinfunction "OUT2B_12") (pintype "output"))
    )
    (net (code "36") (name "P02") (class "Default")
      (node (ref "R31") (pin "1") (pinfunction "1_1") (pintype "passive"))
      (node (ref "U4") (pin "2") (pinfunction "PWM2H1/RP22/CN18/PMA1/RC6_2") (pintype "bidirectional"))
    )
    (net (code "37") (name "P03") (class "Default")
      (node (ref "R29") (pin "1") (pinfunction "1_1") (pintype "passive"))
      (node (ref "U4") (pin "3") (pinfunction "PWM2L1/RP23/CN17/PMA0/RC7_3") (pintype "bidirectional"))
    )
    (net (code "38") (name "P04") (class "Default")
      (node (ref "C22") (pin "1") (pinfunction "1_1") (pintype "passive"))
      (node (ref "J6") (pin "1") (pinfunction "1_1") (pintype "passive"))
      (node (ref "R32") (pin "1") (pinfunction "1_1") (pintype "passive"))
      (node (ref "U4") (pin "4") (pinfunction "RP24/CN20/PMA5/RC8_4") (pintype "bidirectional"))
    )
    (net (code "39") (name "P05") (class "Default")
      (node (ref "J20") (pin "6") (pinfunction "6_6") (pintype "passive"))
      (node (ref "R13") (pin "1") (pinfunction "1_1") (pintype "passive"))
      (node (ref "U4") (pin "5") (pinfunction "RP25/CN19/PMA6/RC9_5") (pintype "bidirectional"))
    )
    (net (code "40") (name "P08") (class "Default")
      (node (ref "J20") (pin "4") (pinfunction "4_4") (pintype "passive"))
      (node (ref "R11") (pin "1") (pinfunction "1_1") (pintype "passive"))
      (node (ref "U4") (pin "8") (pinfunction "PGED2/EMCD2/PWM1H3/RP10/CN16/PMD2/RB10_8") (pintype "bidirectional"))
    )
    (net (code "41") (name "P09") (class "Default")
      (node (ref "J20") (pin "5") (pinfunction "5_5") (pintype "passive"))
      (node (ref "R12") (pin "1") (pinfunction "1_1") (pintype "passive"))
      (node (ref "U4") (pin "9") (pinfunction "PGEC2/EMUC2/PWM1L3/RP11/CN15/PMD1/RB11_9") (pintype "bidirectional"))
    )
    (net (code "42") (name "P10") (class "Default")
      (node (ref "U2") (pin "4") (pinfunction "IN1_4") (pintype "input"))
      (node (ref "U2") (pin "6") (pinfunction "IN3_6") (pintype "input"))
      (node (ref "U4") (pin "10") (pinfunction "PWM1H2/DAC1RP/RP12/CN14/PMD0/RB12_10") (pintype "bidirectional"))
    )
    (net (code "43") (name "P13") (class "Default")
      (node (ref "R23") (pin "1") (pinfunction "1_1") (pintype "passive"))
      (node (ref "U2") (pin "3") (pinfunction "~{SLEEP}_3") (pintype "input"))
      (node (ref "U4") (pin "13") (pinfunction "TCK/PMA7/RA7_13") (pintype "bidirectional"))
    )
    (net (code "44") (name "P14") (class "Default")
      (node (ref "U2") (pin "5") (pinfunction "IN2_5") (pintype "input"))
      (node (ref "U2") (pin "7") (pinfunction "IN4_7") (pintype "input"))
      (node (ref "U4") (pin "14") (pinfunction "PWM1H1/DAC1LP/RTCC/RP14/CN12/PMWR/RB14_14") (pintype "bidirectional"))
    )
    (net (code "45") (name "P18") (class "Default")
      (node (ref "J9") (pin "1") (pinfunction "1_1") (pintype "passive"))
      (node (ref "R7") (pin "2") (pinfunction "2_2") (pintype "passive"))
      (node (ref "U4") (pin "18") (pinfunction "~{MCLR}_18") (pintype "input"))
    )
    (net (code "46") (name "P19") (class "Default")
      (node (ref "R22") (pin "1") (pinfunction "1_1") (pintype "passive"))
      (node (ref "U4") (pin "19") (pinfunction "AN0/VREF+/CN2/RA0_19") (pintype "bidirectional"))
      (node (ref "U5") (pin "1") (pinfunction "SW_1") (pintype "bidirectional"))
    )
    (net (code "47") (name "P21") (class "Default")
      (node (ref "J9") (pin "2") (pinfunction "2_2") (pintype "passive"))
      (node (ref "U4") (pin "21") (pinfunction "PGD1/EMUD1/AN2/C2IN-/RP0/CN4/RB0_21") (pintype "bidirectional"))
    )
    (net (code "48") (name "P22") (class "Default")
      (node (ref "J9") (pin "3") (pinfunction "3_3") (pintype "passive"))
      (node (ref "R26") (pin "1") (pinfunction "1_1") (pintype "passive"))
      (node (ref "U4") (pin "22") (pinfunction "PGC1/EMUC1/AN3/C2IN+/RP1/CN5/RB1_22") (pintype "bidirectional"))
    )
    (net (code "49") (name "P23") (class "Default")
      (node (ref "R38") (pin "1") (pinfunction "1_1") (pintype "passive"))
      (node (ref "U4") (pin "23") (pinfunction "AN4/C1IN-/RP2/CN6/RB2_23") (pintype "bidirectional"))
      (node (ref "U6") (pin "1") (pinfunction "VOUT_1") (pintype "bidirectional"))
    )
    (net (code "50") (name "P24") (class "Default")
      (node (ref "R36") (pin "1") (pinfunction "1_1") (pintype "passive"))
      (node (ref "R45") (pin "1") (pinfunction "1_1") (pintype "passive"))
      (node (ref "U4") (pin "24") (pinfunction "AN5/C1IN+/RP3/CN7/RB3_24") (pintype "bidirectional"))
      (node (ref "U6") (pin "7") (pinfunction "VOUT1_7") (pintype "bidirectional"))
    )
    (net (code "51") (name "P26") (class "Default")
      (node (ref "Q1") (pin "S1") (pinfunction "S_S1") (pintype "bidirectional"))
      (node (ref "Q1") (pin "S2") (pinfunction "S_S2") (pintype "bidirectional"))
      (node (ref "R28") (pin "1") (pinfunction "1_1") (pintype "passive"))
      (node (ref "U4") (pin "26") (pinfunction "AN7/DAC1LM/RP17/CN9/RC1_26") (pintype "bidirectional"))
    )
    (net (code "52") (name "P27") (class "Default")
      (node (ref "J21") (pin "7") (pinfunction "7_7") (pintype "passive"))
      (node (ref "R20") (pin "1") (pinfunction "1_1") (pintype "passive"))
      (node (ref "U4") (pin "27") (pinfunction "AN8/CVREF/RP18/PMA2/CN10/RC2_27") (pintype "bidirectional"))
    )
    (net (code "53") (name "P30") (class "Default")
      (node (ref "J20") (pin "8") (pinfunction "8_8") (pintype "passive"))
      (node (ref "R15") (pin "1") (pinfunction "1_1") (pintype "passive"))
      (node (ref "U4") (pin "30") (pinfunction "OSC1/CLKI/CN30/RA2_30") (pintype "bidirectional"))
    )
    (net (code "54") (name "P31") (class "Default")
      (node (ref "J20") (pin "7") (pinfunction "7_7") (pintype "passive"))
      (node (ref "R14") (pin "1") (pinfunction "1_1") (pintype "passive"))
      (node (ref "U4") (pin "31") (pinfunction "OSC2/CLKO/CN29/RA3_31") (pintype "bidirectional"))
    )
    (net (code "55") (name "P32") (class "Default")
      (node (ref "U4") (pin "32") (pinfunction "TDO/PMA8/RA8_32") (pintype "bidirectional"))
    )
    (net (code "56") (name "P33") (class "Default")
      (node (ref "J21") (pin "9") (pinfunction "9_9") (pintype "passive"))
      (node (ref "R25") (pin "2") (pinfunction "2_2") (pintype "passive"))
      (node (ref "U4") (pin "33") (pinfunction "SOSCI/RP4/CN1/RB4_33") (pintype "bidirectional"))
    )
    (net (code "57") (name "P34") (class "Default")
      (node (ref "Q4") (pin "1") (pinfunction "G_1") (pintype "passive"))
      (node (ref "U4") (pin "34") (pinfunction "SOSCO/T1CK/CN0/RA4_34") (pintype "bidirectional"))
    )
    (net (code "58") (name "P35") (class "Default")
      (node (ref "U4") (pin "35") (pinfunction "TDI/PMA9/RA9_35") (pintype "bidirectional"))
    )
    (net (code "59") (name "P36") (class "Default")
      (node (ref "Q3") (pin "G2") (pinfunction "G_G2") (pintype "bidirectional"))
      (node (ref "R9") (pin "1") (pinfunction "1_1") (pintype "passive"))
      (node (ref "U4") (pin "36") (pinfunction "RP19/CN28/PMBE/RC3_36") (pintype "bidirectional"))
    )
    (net (code "60") (name "P37") (class "Default")
      (node (ref "Q3") (pin "G1") (pinfunction "G_G1") (pintype "bidirectional"))
      (node (ref "R8") (pin "1") (pinfunction "1_1") (pintype "passive"))
      (node (ref "U4") (pin "37") (pinfunction "RP20/CN25/PMA4/RC4_37") (pintype "bidirectional"))
    )
    (net (code "61") (name "P38") (class "Default")
      (node (ref "J21") (pin "8") (pinfunction "8_8") (pintype "passive"))
      (node (ref "R21") (pin "1") (pinfunction "1_1") (pintype "passive"))
      (node (ref "U4") (pin "38") (pinfunction "RP21/CN26/PMA3/RC5_38") (pintype "bidirectional"))
    )
    (net (code "62") (name "P41") (class "Default")
      (node (ref "U2") (pin "8") (pinfunction "FL1_8") (pintype "input"))
      (node (ref "U2") (pin "9") (pinfunction "FL2_9") (pintype "input"))
      (node (ref "U4") (pin "41") (pinfunction "PGED3/EMUD3/ASDA1/RP5/CN27/PMD7/RB5_41") (pintype "bidirectional"))
    )
    (net (code "63") (name "SCL") (class "Default")
      (node (ref "J1") (pin "5") (pinfunction "5_5") (pintype "passive"))
      (node (ref "J2") (pin "5") (pinfunction "5_5") (pintype "passive"))
      (node (ref "J3") (pin "5") (pinfunction "5_5") (pintype "passive"))
      (node (ref "J4") (pin "5") (pinfunction "5_5") (pintype "passive"))
      (node (ref "R35") (pin "1") (pinfunction "1_1") (pintype "passive"))
      (node (ref "U3") (pin "3") (pinfunction "SCL1_3") (pintype "bidirectional"))
      (node (ref "U4") (pin "44") (pinfunction "SCL1/RP8/CN22/PMD4/RB8_44") (pintype "bidirectional"))
    )
    (net (code "64") (name "SDA") (class "Default")
      (node (ref "J1") (pin "4") (pinfunction "4_4") (pintype "passive"))
      (node (ref "J2") (pin "4") (pinfunction "4_4") (pintype "passive"))
      (node (ref "J3") (pin "4") (pinfunction "4_4") (pintype "passive"))
      (node (ref "J4") (pin "4") (pinfunction "4_4") (pintype "passive"))
      (node (ref "R34") (pin "1") (pinfunction "1_1") (pintype "passive"))
      (node (ref "U3") (pin "2") (pinfunction "SDA1_2") (pintype "bidirectional"))
      (node (ref "U4") (pin "1") (pinfunction "SDA1/RP9/CN21/PMD3/RB9_1") (pintype "bidirectional"))
    )
    (net (code "65") (name "VBAT") (class "Default")
      (node (ref "C16") (pin "1") (pinfunction "1_1") (pintype "passive"))
      (node (ref "C2") (pin "1") (pinfunction "1_1") (pintype "passive"))
      (node (ref "C8") (pin "1") (pinfunction "1_1") (pintype "passive"))
      (node (ref "IC2") (pin "1") (pinfunction "IN_1") (pintype "input"))
      (node (ref "IC3") (pin "1") (pinfunction "IN_1") (pintype "input"))
      (node (ref "J5") (pin "1") (pinfunction "2_1") (pintype "passive"))
      (node (ref "L2") (pin "1") (pinfunction "1_1") (pintype "passive"))
      (node (ref "R10") (pin "2") (pinfunction "2_2") (pintype "passive"))
      (node (ref "U1") (pin "2") (pinfunction "VIN1_2") (pintype "input"))
      (node (ref "U1") (pin "3") (pinfunction "VIN2_3") (pintype "input"))
      (node (ref "U1") (pin "4") (pinfunction "EN_4") (pintype "input"))
    )
    (net (code "66") (name "VC1") (class "Default")
      (node (ref "IC2") (pin "3") (pinfunction "EN_3") (pintype "input"))
      (node (ref "J2") (pin "2") (pinfunction "2_2") (pintype "passive"))
      (node (ref "J4") (pin "2") (pinfunction "2_2") (pintype "passive"))
      (node (ref "Q3") (pin "D1") (pinfunction "D_D1") (pintype "bidirectional"))
    )
    (net (code "67") (name "VC2") (class "Default")
      (node (ref "IC3") (pin "3") (pinfunction "EN_3") (pintype "input"))
      (node (ref "J1") (pin "2") (pinfunction "2_2") (pintype "passive"))
      (node (ref "J3") (pin "2") (pinfunction "2_2") (pintype "passive"))
      (node (ref "Q3") (pin "D2") (pinfunction "D_D2") (pintype "bidirectional"))
    )
    (net (code "68") (name "VD1") (class "Default")
      (node (ref "C7") (pin "1") (pinfunction "1_1") (pintype "passive"))
      (node (ref "IC2") (pin "5") (pinfunction "OUT_5") (pintype "output"))
      (node (ref "J2") (pin "3") (pinfunction "3_3") (pintype "passive"))
      (node (ref "J4") (pin "3") (pinfunction "3_3") (pintype "passive"))
      (node (ref "J7") (pin "4") (pinfunction "4_4") (pintype "passive"))
    )
    (net (code "69") (name "VD2") (class "Default")
      (node (ref "C9") (pin "1") (pinfunction "1_1") (pintype "passive"))
      (node (ref "IC3") (pin "5") (pinfunction "OUT_5") (pintype "output"))
      (node (ref "J1") (pin "3") (pinfunction "3_3") (pintype "passive"))
      (node (ref "J3") (pin "3") (pinfunction "3_3") (pintype "passive"))
    )
    (net (code "70") (name "VDD") (class "Default")
      (node (ref "C12") (pin "1") (pinfunction "1_1") (pintype "passive"))
      (node (ref "C14") (pin "1") (pinfunction "1_1") (pintype "passive"))
      (node (ref "C17") (pin "1") (pinfunction "1_1") (pintype "passive"))
      (node (ref "C23") (pin "1") (pinfunction "1_1") (pintype "passive"))
      (node (ref "C24") (pin "1") (pinfunction "1_1") (pintype "passive"))
      (node (ref "C25") (pin "1") (pinfunction "1_1") (pintype "passive"))
      (node (ref "C4") (pin "1") (pinfunction "1_1") (pintype "passive"))
      (node (ref "C5") (pin "1") (pinfunction "1_1") (pintype "passive"))
      (node (ref "C6") (pin "1") (pinfunction "1_1") (pintype "passive"))
      (node (ref "D1") (pin "3") (pinfunction "K_3") (pintype "passive"))
      (node (ref "J20") (pin "3") (pinfunction "3_3") (pintype "passive"))
      (node (ref "L1") (pin "2") (pinfunction "2_2") (pintype "passive"))
      (node (ref "M1") (pin "POS") (pinfunction "POS_POS") (pintype "bidirectional"))
      (node (ref "Q3") (pin "S1") (pinfunction "S_S1") (pintype "bidirectional"))
      (node (ref "Q3") (pin "S2") (pinfunction "S_S2") (pintype "bidirectional"))
      (node (ref "R11") (pin "2") (pinfunction "2_2") (pintype "passive"))
      (node (ref "R12") (pin "2") (pinfunction "2_2") (pintype "passive"))
      (node (ref "R13") (pin "2") (pinfunction "2_2") (pintype "passive"))
      (node (ref "R14") (pin "2") (pinfunction "2_2") (pintype "passive"))
      (node (ref "R15") (pin "2") (pinfunction "2_2") (pintype "passive"))
      (node (ref "R18") (pin "1") (pinfunction "1_1") (pintype "passive"))
      (node (ref "R19") (pin "1") (pinfunction "1_1") (pintype "passive"))
      (node (ref "R20") (pin "2") (pinfunction "2_2") (pintype "passive"))
      (node (ref "R21") (pin "2") (pinfunction "2_2") (pintype "passive"))
      (node (ref "R25") (pin "1") (pinfunction "1_1") (pintype "passive"))
      (node (ref "R26") (pin "2") (pinfunction "2_2") (pintype "passive"))
      (node (ref "R28") (pin "2") (pinfunction "2_2") (pintype "passive"))
      (node (ref "R3") (pin "1") (pinfunction "1_1") (pintype "passive"))
      (node (ref "R32") (pin "2") (pinfunction "2_2") (pintype "passive"))
      (node (ref "R34") (pin "2") (pinfunction "2_2") (pintype "passive"))
      (node (ref "R35") (pin "2") (pinfunction "2_2") (pintype "passive"))
      (node (ref "R36") (pin "2") (pinfunction "2_2") (pintype "passive"))
      (node (ref "R6") (pin "1") (pinfunction "1_1") (pintype "passive"))
      (node (ref "R8") (pin "2") (pinfunction "2_2") (pintype "passive"))
      (node (ref "R9") (pin "2") (pinfunction "2_2") (pintype "passive"))
      (node (ref "U3") (pin "1") (pinfunction "VDD1_1") (pintype "power_in"))
      (node (ref "U4") (pin "17") (pinfunction "AVDD_17") (pintype "power_in"))
      (node (ref "U4") (pin "28") (pinfunction "VDD_2_28") (pintype "power_in"))
      (node (ref "U4") (pin "40") (pinfunction "VDD_40") (pintype "power_in"))
      (node (ref "U5") (pin "5") (pinfunction "VIN_5") (pintype "power_in"))
      (node (ref "U6") (pin "8") (pinfunction "VDD_8") (pintype "power_in"))
    )
    (net (code "71") (name "VM") (class "Default")
      (node (ref "C13") (pin "2") (pinfunction "2_2") (pintype "passive"))
      (node (ref "C18") (pin "1") (pinfunction "1_1") (pintype "passive"))
      (node (ref "J1") (pin "1") (pinfunction "1_1") (pintype "passive"))
      (node (ref "J2") (pin "1") (pinfunction "1_1") (pintype "passive"))
      (node (ref "J3") (pin "1") (pinfunction "1_1") (pintype "passive"))
      (node (ref "J4") (pin "1") (pinfunction "1_1") (pintype "passive"))
      (node (ref "J9") (pin "5") (pinfunction "5_5") (pintype "passive"))
      (node (ref "Q2") (pin "5-8") (pinfunction "D_5-8") (pintype "passive"))
      (node (ref "R1") (pin "2") (pinfunction "2_2") (pintype "passive"))
      (node (ref "R27") (pin "2") (pinfunction "2_2") (pintype "passive"))
      (node (ref "U2") (pin "13") (pinfunction "VBB_13") (pintype "power_in"))
    )
    (net (code "72") (name "unconnected-(IC2-ADJ-Pad4)") (class "Default")
      (node (ref "IC2") (pin "4") (pinfunction "ADJ_4") (pintype "passive"))
    )
    (net (code "73") (name "unconnected-(IC3-ADJ-Pad4)") (class "Default")
      (node (ref "IC3") (pin "4") (pinfunction "ADJ_4") (pintype "passive"))
    )
    (net (code "74") (name "unconnected-(J20-Pad1)") (class "Default")
      (node (ref "J20") (pin "1") (pinfunction "1_1") (pintype "passive"))
    )
    (net (code "75") (name "unconnected-(J20-Pad9)") (class "Default")
      (node (ref "J20") (pin "9") (pinfunction "9_9") (pintype "passive"))
    )
    (net (code "76") (name "unconnected-(J21-Pad2)") (class "Default")
      (node (ref "J21") (pin "2") (pinfunction "2_2") (pintype "passive"))
    )
    (net (code "77") (name "unconnected-(J21-Pad3)") (class "Default")
      (node (ref "J21") (pin "3") (pinfunction "3_3") (pintype "passive"))
    )
    (net (code "78") (name "unconnected-(J21-Pad4)") (class "Default")
      (node (ref "J21") (pin "4") (pinfunction "4_4") (pintype "passive"))
    )
    (net (code "79") (name "unconnected-(U1-FB-Pad10)") (class "Default")
      (node (ref "U1") (pin "10") (pinfunction "FB_10") (pintype "bidirectional"))
    )
    (net (code "80") (name "unconnected-(U1-LBI-Pad7)") (class "Default")
      (node (ref "U1") (pin "7") (pinfunction "LBI_7") (pintype "input"))
    )
    (net (code "81") (name "unconnected-(U1-LBO-Pad6)") (class "Default")
      (node (ref "U1") (pin "6") (pinfunction "LBO_6") (pintype "bidirectional"))
    )
    (net (code "82") (name "unconnected-(U1-PG-Pad13)") (class "Default")
      (node (ref "U1") (pin "13") (pinfunction "PG_13") (pintype "bidirectional"))
    )
    (net (code "83") (name "unconnected-(U1-VINA-Pad8)") (class "Default")
      (node (ref "U1") (pin "8") (pinfunction "VINA_8") (pintype "input"))
    )
    (net (code "84") (name "unconnected-(U2-OUT1A-Pad16)") (class "Default")
      (node (ref "U2") (pin "16") (pinfunction "OUT1A_16") (pintype "output"))
    )
    (net (code "85") (name "unconnected-(U2-OUT1B-Pad14)") (class "Default")
      (node (ref "U2") (pin "14") (pinfunction "OUT1B_14") (pintype "output"))
    )
    (net (code "86") (name "unconnected-(U2-PadEXP)") (class "Default")
      (node (ref "U2") (pin "EXP") (pinfunction "EXP_EXP") (pintype "passive"))
    )
    (net (code "87") (name "unconnected-(U4-PWM1L1{slash}DAC1LN{slash}RP15{slash}CN11{slash}PMCS1{slash}RB15-Pad15)") (class "Default")
      (node (ref "U4") (pin "15") (pinfunction "PWM1L1/DAC1LN/RP15/CN11/PMCS1/RB15_15") (pintype "bidirectional"))
    )
    (net (code "88") (name "unconnected-(U4-PWM1L2{slash}DAC1RN{slash}RP13{slash}CN13{slash}PMRD{slash}RB13-Pad11)") (class "Default")
      (node (ref "U4") (pin "11") (pinfunction "PWM1L2/DAC1RN/RP13/CN13/PMRD/RB13_11") (pintype "bidirectional"))
    )
    (net (code "89") (name "unconnected-(U4-TMS{slash}PMA10{slash}RA10-Pad12)") (class "Default")
      (node (ref "U4") (pin "12") (pinfunction "TMS/PMA10/RA10_12") (pintype "bidirectional"))
    )
  )
)
